# Plato_soldadura_328P.net
KiCad netlist of a schematic drawn in EAGLE
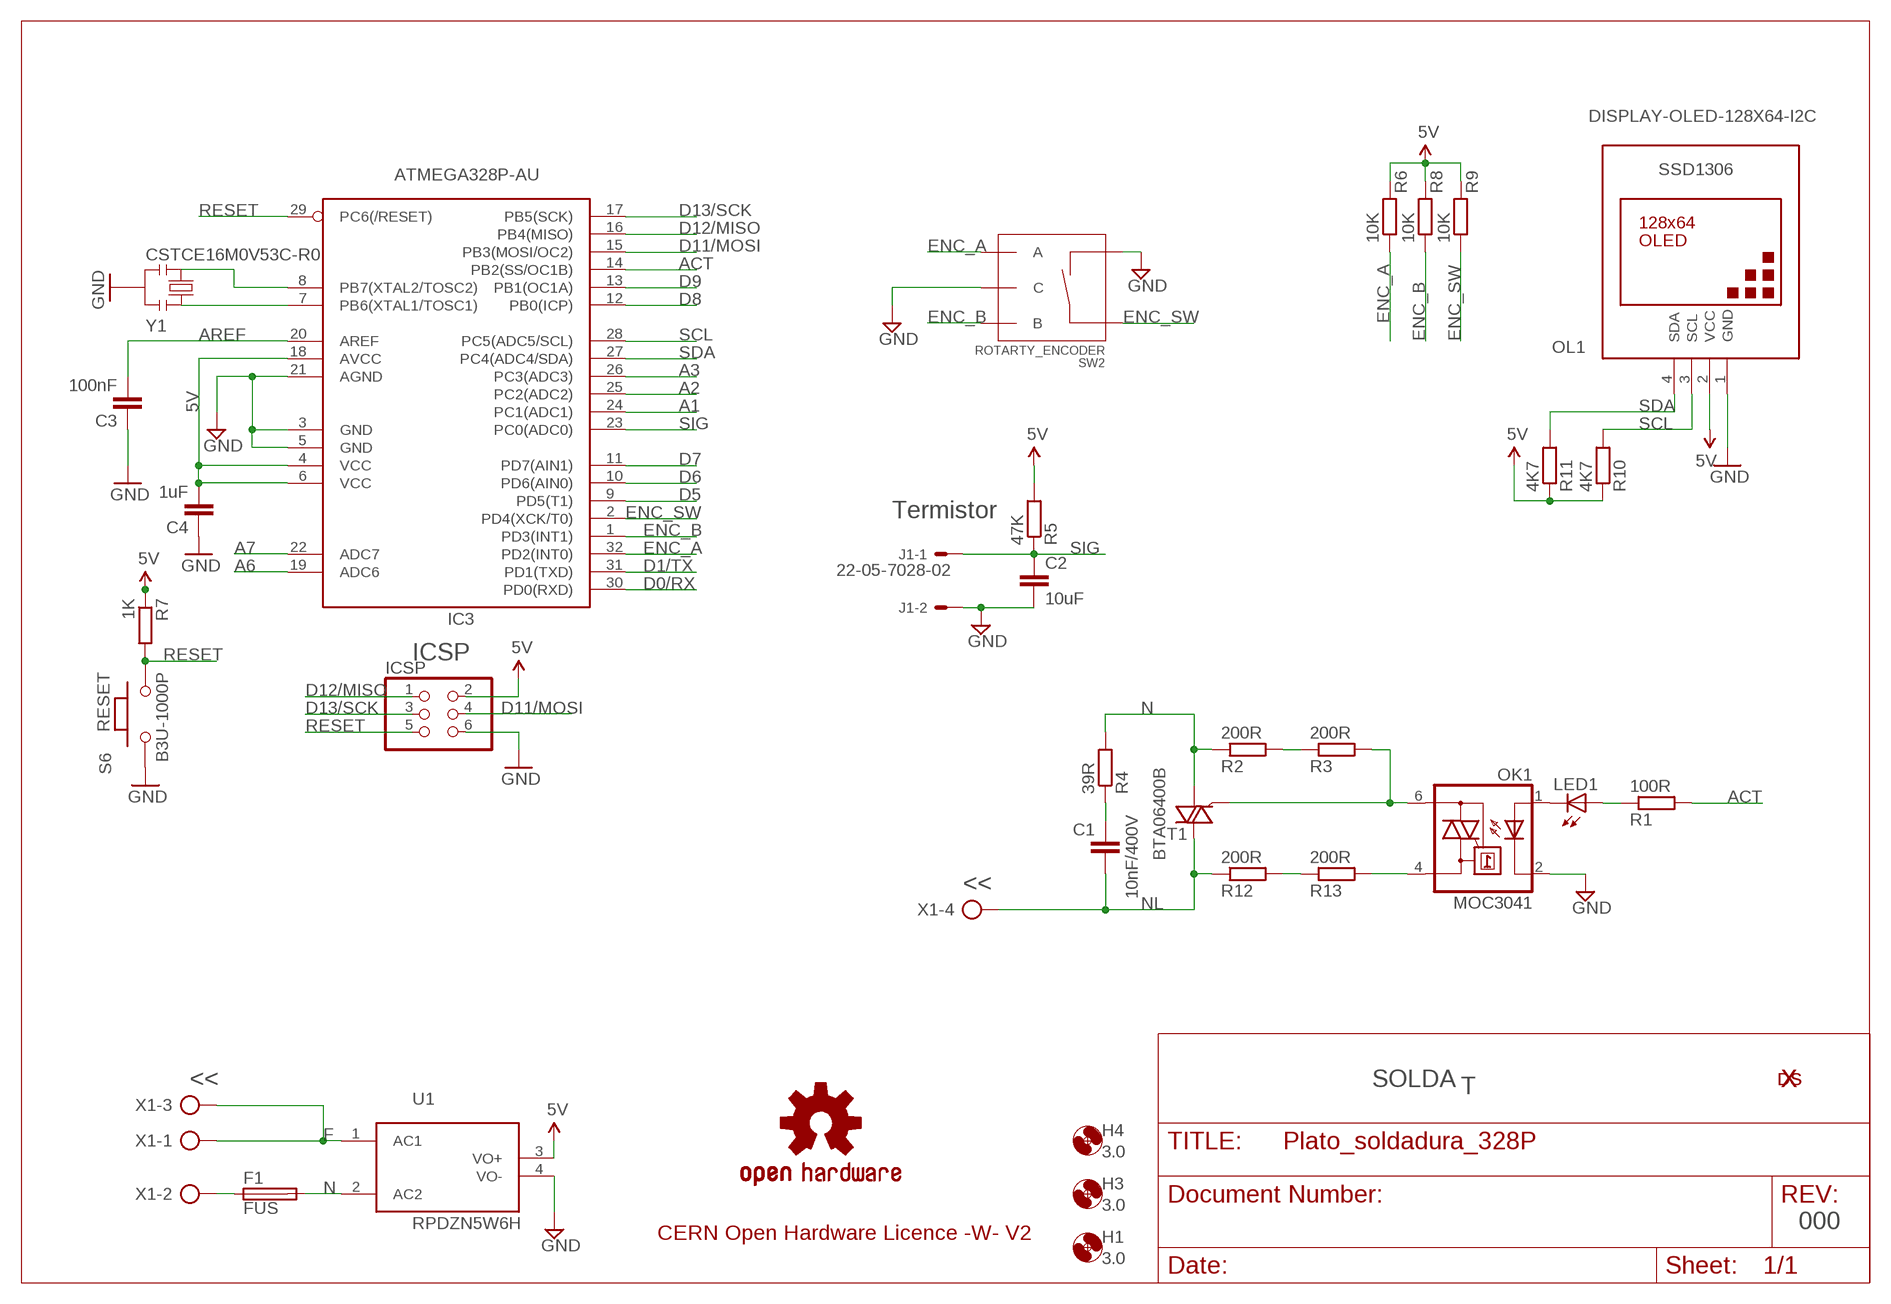
[diagram p0: schematic, sheet 1]

(export (version "E")
  (design (tool "Eeschema 10.0.6"))
  (components
    (comp (ref "C1")
      (value "10nF/400V")
      (footprint "eagle-import:C075-042X103")
      (libsource (lib "eagle-import") (part "C-EU075-042X103"))
    )
    (comp (ref "C2")
      (value "10uF")
      (footprint "eagle-import:C1206")
      (libsource (lib "eagle-import") (part "C-EUC1206"))
    )
    (comp (ref "C3")
      (value "100nF")
      (footprint "eagle-import:C0603")
      (libsource (lib "eagle-import") (part "C-EUC0603"))
    )
    (comp (ref "C4")
      (value "1uF")
      (footprint "eagle-import:C0603")
      (libsource (lib "eagle-import") (part "C-EUC0603"))
    )
    (comp (ref "F1")
      (value "FUS")
      (footprint "eagle-import:TE5")
      (libsource (lib "eagle-import") (part "FUSETE5"))
    )
    (comp (ref "H1")
      (value "3.0")
      (footprint "eagle-import:3,0")
      (libsource (lib "eagle-import") (part "MOUNT-HOLE3.0"))
    )
    (comp (ref "H3")
      (value "3.0")
      (footprint "eagle-import:3,0")
      (libsource (lib "eagle-import") (part "MOUNT-HOLE3.0"))
    )
    (comp (ref "H4")
      (value "3.0")
      (footprint "eagle-import:3,0")
      (libsource (lib "eagle-import") (part "MOUNT-HOLE3.0"))
    )
    (comp (ref "IC3")
      (value "ATMEGA328P-AU")
      (footprint "eagle-import:TQFP32-08")
      (libsource (lib "eagle-import") (part "0265_ATMEGA328P-AU"))
    )
    (comp (ref "ICSP")
      (value "0114_PH254-203DF118A00V")
      (footprint "eagle-import:2X03")
      (fields (field (name "PART_NUMBER") "PH254-203DF118A00V"))
      (libsource (lib "eagle-import") (part "0114_PH254-203DF118A00V"))
    )
    (comp (ref "J1")
      (value "22-05-7028-02")
      (footprint "eagle-import:7395-02")
      (libsource (lib "eagle-import") (part "22-?-0205-7028"))
    )
    (comp (ref "LED1")
      (value "LEDCHIP-LED0603")
      (footprint "eagle-import:CHIP-LED0603")
      (libsource (lib "eagle-import") (part "LEDCHIP-LED0603"))
    )
    (comp (ref "LOGO2")
      (value "OSHW-LOGOL")
      (footprint "eagle-import:ESCORNA_LBRESCORNA_CPU_2_10_SPARKFUN-AESTHETICS_OSHW-LOGO-L")
      (libsource (lib "eagle-import") (part "OSHW-LOGOL"))
    )
    (comp (ref "OK1")
      (value "MOC3041")
      (footprint "eagle-import:DIL06")
      (fields (field (name "MF") "VISHAY/TELEFUNKEN") (field (name "MPN") "IL410"))
      (libsource (lib "eagle-import") (part "IL410"))
    )
    (comp (ref "OL1")
      (value "DISPLAY-OLED-128X64-I2C")
      (footprint "eagle-import:DISPLAY-OLED-128X64-I2C")
      (libsource (lib "eagle-import") (part "DISPLAY-OLED-128X64-I2C"))
    )
    (comp (ref "R1")
      (value "100R")
      (footprint "eagle-import:R0603")
      (libsource (lib "eagle-import") (part "R-EU_R0603"))
    )
    (comp (ref "R2")
      (value "200R")
      (footprint "eagle-import:R1206")
      (libsource (lib "eagle-import") (part "R-EU_R1206"))
    )
    (comp (ref "R3")
      (value "200R")
      (footprint "eagle-import:R1206")
      (libsource (lib "eagle-import") (part "R-EU_R1206"))
    )
    (comp (ref "R4")
      (value "39R")
      (footprint "eagle-import:0204_7")
      (libsource (lib "eagle-import") (part "R-EU_0204/7"))
    )
    (comp (ref "R5")
      (value "47K")
      (footprint "eagle-import:R0603")
      (libsource (lib "eagle-import") (part "R-EU_R0603"))
    )
    (comp (ref "R6")
      (value "10K")
      (footprint "eagle-import:R0603")
      (libsource (lib "eagle-import") (part "R-EU_R0603"))
    )
    (comp (ref "R7")
      (value "1K")
      (footprint "eagle-import:R0603")
      (libsource (lib "eagle-import") (part "R-EU_R0603"))
    )
    (comp (ref "R8")
      (value "10K")
      (footprint "eagle-import:R0603")
      (libsource (lib "eagle-import") (part "R-EU_R0603"))
    )
    (comp (ref "R9")
      (value "10K")
      (footprint "eagle-import:R0603")
      (libsource (lib "eagle-import") (part "R-EU_R0603"))
    )
    (comp (ref "R10")
      (value "4K7")
      (footprint "eagle-import:R0603")
      (libsource (lib "eagle-import") (part "R-EU_R0603"))
    )
    (comp (ref "R11")
      (value "4K7")
      (footprint "eagle-import:R0603")
      (libsource (lib "eagle-import") (part "R-EU_R0603"))
    )
    (comp (ref "R12")
      (value "200R")
      (footprint "eagle-import:R1206")
      (libsource (lib "eagle-import") (part "R-EU_R1206"))
    )
    (comp (ref "R13")
      (value "200R")
      (footprint "eagle-import:R1206")
      (libsource (lib "eagle-import") (part "R-EU_R1206"))
    )
    (comp (ref "S6")
      (value "B3U-1000P")
      (footprint "eagle-import:SMD_157SW")
      (fields (field (name "PART_NUMBER") "IT-1185AP1C-160G-G_T&R"))
      (libsource (lib "eagle-import") (part "0173_IT-1185AP1C-160G-G_T&R"))
    )
    (comp (ref "SW2")
      (value "ROTARTY_ENCODER")
      (footprint "eagle-import:ROTARY_ENC_PLAIN")
      (libsource (lib "eagle-import") (part "ROTARTY_ENCODER"))
    )
    (comp (ref "T1")
      (value "BTA06400B")
      (footprint "eagle-import:TO220AB")
      (libsource (lib "eagle-import") (part "BT136"))
    )
    (comp (ref "U$7")
      (value "XDESIG_XDESIG5MM")
      (footprint "eagle-import:XDESIG_XDESIG_CU")
      (libsource (lib "eagle-import") (part "XDESIG_XDESIG5MM"))
    )
    (comp (ref "U$8")
      (value "XDESIG_XDESIG21")
      (footprint "eagle-import:XDESIG_XDESIG")
      (libsource (lib "eagle-import") (part "XDESIG_XDESIG21"))
    )
    (comp (ref "U1")
      (value "RPDZN5W6H")
      (footprint "eagle-import:RPDZN5W6H")
      (libsource (lib "eagle-import") (part "RPDZN5W6H"))
    )
    (comp (ref "X1")
      (value "AK500/4-H")
      (footprint "eagle-import:AK500_4-H")
      (libsource (lib "eagle-import") (part "AK500/4-H"))
    )
    (comp (ref "Y1")
      (value "CSTCE16M0V53C-R0")
      (footprint "eagle-import:RESONATOR")
      (fields (field (name "PART_NUMBER") "CSTCE16M0V53-R0"))
      (libsource (lib "eagle-import") (part "0011_CSTCE16M0V53-R0"))
    )
  )
  (nets
    (net (code "1") (name "/A1") (class "Default")
      (node (ref "IC3") (pin "24") (pinfunction "PC1(ADC1)_24") (pintype "bidirectional"))
    )
    (net (code "2") (name "/A2") (class "Default")
      (node (ref "IC3") (pin "25") (pinfunction "PC2(ADC2)_25") (pintype "bidirectional"))
    )
    (net (code "3") (name "/A3") (class "Default")
      (node (ref "IC3") (pin "26") (pinfunction "PC3(ADC3)_26") (pintype "bidirectional"))
    )
    (net (code "4") (name "/A6") (class "Default")
      (node (ref "IC3") (pin "19") (pinfunction "ADC6_19") (pintype "bidirectional"))
    )
    (net (code "5") (name "/A7") (class "Default")
      (node (ref "IC3") (pin "22") (pinfunction "ADC7_22") (pintype "bidirectional"))
    )
    (net (code "6") (name "/ACT") (class "Default")
      (node (ref "IC3") (pin "14") (pinfunction "PB2(SS/OC1B)_14") (pintype "bidirectional"))
      (node (ref "R1") (pin "2") (pinfunction "2_2") (pintype "passive"))
    )
    (net (code "7") (name "/AREF") (class "Default")
      (node (ref "C3") (pin "2") (pinfunction "2_2") (pintype "passive"))
      (node (ref "IC3") (pin "20") (pinfunction "AREF_20") (pintype "bidirectional"))
    )
    (net (code "8") (name "/D0{slash}RX") (class "Default")
      (node (ref "IC3") (pin "30") (pinfunction "PD0(RXD)_30") (pintype "bidirectional"))
    )
    (net (code "9") (name "/D1{slash}TX") (class "Default")
      (node (ref "IC3") (pin "31") (pinfunction "PD1(TXD)_31") (pintype "bidirectional"))
    )
    (net (code "10") (name "/D5") (class "Default")
      (node (ref "IC3") (pin "9") (pinfunction "PD5(T1)_9") (pintype "bidirectional"))
    )
    (net (code "11") (name "/D6") (class "Default")
      (node (ref "IC3") (pin "10") (pinfunction "PD6(AIN0)_10") (pintype "bidirectional"))
    )
    (net (code "12") (name "/D7") (class "Default")
      (node (ref "IC3") (pin "11") (pinfunction "PD7(AIN1)_11") (pintype "bidirectional"))
    )
    (net (code "13") (name "/D8") (class "Default")
      (node (ref "IC3") (pin "12") (pinfunction "PB0(ICP)_12") (pintype "bidirectional"))
    )
    (net (code "14") (name "/D9") (class "Default")
      (node (ref "IC3") (pin "13") (pinfunction "PB1(OC1A)_13") (pintype "bidirectional"))
    )
    (net (code "15") (name "/D11{slash}MOSI") (class "Default")
      (node (ref "IC3") (pin "15") (pinfunction "PB3(MOSI/OC2)_15") (pintype "bidirectional"))
      (node (ref "ICSP") (pin "4") (pinfunction "4_4") (pintype "passive"))
    )
    (net (code "16") (name "/D12{slash}MISO") (class "Default")
      (node (ref "IC3") (pin "16") (pinfunction "PB4(MISO)_16") (pintype "bidirectional"))
      (node (ref "ICSP") (pin "1") (pinfunction "1_1") (pintype "passive"))
    )
    (net (code "17") (name "/D13{slash}SCK") (class "Default")
      (node (ref "IC3") (pin "17") (pinfunction "PB5(SCK)_17") (pintype "bidirectional"))
      (node (ref "ICSP") (pin "3") (pinfunction "3_3") (pintype "passive"))
    )
    (net (code "18") (name "/ENC_A") (class "Default")
      (node (ref "IC3") (pin "32") (pinfunction "PD2(INT0)_32") (pintype "bidirectional"))
      (node (ref "R6") (pin "1") (pinfunction "1_1") (pintype "passive"))
      (node (ref "SW2") (pin "A") (pinfunction "A_A") (pintype "bidirectional"))
    )
    (net (code "19") (name "/ENC_B") (class "Default")
      (node (ref "IC3") (pin "1") (pinfunction "PD3(INT1)_1") (pintype "bidirectional"))
      (node (ref "R8") (pin "1") (pinfunction "1_1") (pintype "passive"))
      (node (ref "SW2") (pin "B") (pinfunction "B_B") (pintype "bidirectional"))
    )
    (net (code "20") (name "/ENC_SW") (class "Default")
      (node (ref "IC3") (pin "2") (pinfunction "PD4(XCK/T0)_2") (pintype "bidirectional"))
      (node (ref "R9") (pin "1") (pinfunction "1_1") (pintype "passive"))
      (node (ref "SW2") (pin "SW+") (pinfunction "SW+_SW+") (pintype "bidirectional"))
    )
    (net (code "21") (name "/F") (class "Default")
      (node (ref "U1") (pin "1") (pinfunction "AC1_1") (pintype "bidirectional"))
      (node (ref "X1") (pin "1") (pinfunction "KL_1") (pintype "passive"))
      (node (ref "X1") (pin "3") (pinfunction "KL_3") (pintype "passive"))
    )
    (net (code "22") (name "/N") (class "Default")
      (node (ref "F1") (pin "2") (pinfunction "2_2") (pintype "passive"))
      (node (ref "R2") (pin "1") (pinfunction "1_1") (pintype "passive"))
      (node (ref "R4") (pin "2") (pinfunction "2_2") (pintype "passive"))
      (node (ref "T1") (pin "1") (pinfunction "A1_1") (pintype "passive"))
      (node (ref "U1") (pin "2") (pinfunction "AC2_2") (pintype "bidirectional"))
    )
    (net (code "23") (name "/NL") (class "Default")
      (node (ref "C1") (pin "2") (pinfunction "2_2") (pintype "passive"))
      (node (ref "R12") (pin "1") (pinfunction "1_1") (pintype "passive"))
      (node (ref "T1") (pin "2") (pinfunction "A2_2") (pintype "passive"))
      (node (ref "X1") (pin "4") (pinfunction "KL_4") (pintype "passive"))
    )
    (net (code "24") (name "/RESET") (class "Default")
      (node (ref "IC3") (pin "29") (pinfunction "PC6(/RESET)_29") (pintype "bidirectional"))
      (node (ref "ICSP") (pin "5") (pinfunction "5_5") (pintype "passive"))
      (node (ref "R7") (pin "2") (pinfunction "2_2") (pintype "passive"))
      (node (ref "S6") (pin "2") (pinfunction "2_2") (pintype "passive"))
    )
    (net (code "25") (name "/SCL") (class "Default")
      (node (ref "IC3") (pin "28") (pinfunction "PC5(ADC5/SCL)_28") (pintype "bidirectional"))
      (node (ref "OL1") (pin "3") (pinfunction "SCL_3") (pintype "bidirectional"))
      (node (ref "R10") (pin "2") (pinfunction "2_2") (pintype "passive"))
    )
    (net (code "26") (name "/SDA") (class "Default")
      (node (ref "IC3") (pin "27") (pinfunction "PC4(ADC4/SDA)_27") (pintype "bidirectional"))
      (node (ref "OL1") (pin "4") (pinfunction "SDA_4") (pintype "bidirectional"))
      (node (ref "R11") (pin "2") (pinfunction "2_2") (pintype "passive"))
    )
    (net (code "27") (name "/SIG") (class "Default")
      (node (ref "C2") (pin "1") (pinfunction "1_1") (pintype "passive"))
      (node (ref "IC3") (pin "23") (pinfunction "PC0(ADC0)_23") (pintype "bidirectional"))
      (node (ref "J1") (pin "1") (pinfunction "S_1") (pintype "passive"))
      (node (ref "R5") (pin "1") (pinfunction "1_1") (pintype "passive"))
    )
    (net (code "28") (name "5V") (class "Default")
      (node (ref "C4") (pin "2") (pinfunction "2_2") (pintype "passive"))
      (node (ref "IC3") (pin "18") (pinfunction "AVCC_18") (pintype "bidirectional"))
      (node (ref "IC3") (pin "4") (pinfunction "VCC_4") (pintype "bidirectional"))
      (node (ref "IC3") (pin "6") (pinfunction "VCC_6") (pintype "bidirectional"))
      (node (ref "ICSP") (pin "2") (pinfunction "2_2") (pintype "passive"))
      (node (ref "OL1") (pin "2") (pinfunction "VCC_2") (pintype "power_in"))
      (node (ref "R10") (pin "1") (pinfunction "1_1") (pintype "passive"))
      (node (ref "R11") (pin "1") (pinfunction "1_1") (pintype "passive"))
      (node (ref "R5") (pin "2") (pinfunction "2_2") (pintype "passive"))
      (node (ref "R6") (pin "2") (pinfunction "2_2") (pintype "passive"))
      (node (ref "R7") (pin "1") (pinfunction "1_1") (pintype "passive"))
      (node (ref "R8") (pin "2") (pinfunction "2_2") (pintype "passive"))
      (node (ref "R9") (pin "2") (pinfunction "2_2") (pintype "passive"))
      (node (ref "U1") (pin "3") (pinfunction "VO+_3") (pintype "bidirectional"))
    )
    (net (code "29") (name "GND") (class "Default")
      (node (ref "C2") (pin "2") (pinfunction "2_2") (pintype "passive"))
      (node (ref "C3") (pin "1") (pinfunction "1_1") (pintype "passive"))
      (node (ref "C4") (pin "1") (pinfunction "1_1") (pintype "passive"))
      (node (ref "IC3") (pin "21") (pinfunction "AGND_21") (pintype "bidirectional"))
      (node (ref "IC3") (pin "3") (pinfunction "GND_3") (pintype "bidirectional"))
      (node (ref "IC3") (pin "5") (pinfunction "GND_5") (pintype "bidirectional"))
      (node (ref "ICSP") (pin "6") (pinfunction "6_6") (pintype "passive"))
      (node (ref "J1") (pin "2") (pinfunction "S_2") (pintype "passive"))
      (node (ref "OK1") (pin "2") (pinfunction "C_2") (pintype "passive"))
      (node (ref "OL1") (pin "1") (pinfunction "GND_1") (pintype "power_in"))
      (node (ref "S6") (pin "1") (pinfunction "1_1") (pintype "passive"))
      (node (ref "SW2") (pin "C") (pinfunction "C_C") (pintype "bidirectional"))
      (node (ref "SW2") (pin "SW-") (pinfunction "SW-_SW-") (pintype "bidirectional"))
      (node (ref "U1") (pin "4") (pinfunction "VO-_4") (pintype "bidirectional"))
      (node (ref "Y1") (pin "2") (pinfunction "2_2") (pintype "passive"))
    )
    (net (code "30") (name "Net-(C1-Pad1)") (class "Default")
      (node (ref "C1") (pin "1") (pinfunction "1_1") (pintype "passive"))
      (node (ref "R4") (pin "1") (pinfunction "1_1") (pintype "passive"))
    )
    (net (code "31") (name "Net-(IC3-PB6(XTAL1{slash}TOSC1))") (class "Default")
      (node (ref "IC3") (pin "7") (pinfunction "PB6(XTAL1/TOSC1)_7") (pintype "bidirectional"))
      (node (ref "Y1") (pin "1") (pinfunction "1_1") (pintype "passive"))
    )
    (net (code "32") (name "Net-(IC3-PB7(XTAL2{slash}TOSC2))") (class "Default")
      (node (ref "IC3") (pin "8") (pinfunction "PB7(XTAL2/TOSC2)_8") (pintype "bidirectional"))
      (node (ref "Y1") (pin "3") (pinfunction "3_3") (pintype "passive"))
    )
    (net (code "33") (name "Net-(LED1-PadA)") (class "Default")
      (node (ref "LED1") (pin "A") (pinfunction "A_A") (pintype "passive"))
      (node (ref "R1") (pin "1") (pinfunction "1_1") (pintype "passive"))
    )
    (net (code "34") (name "Net-(OK1-A)") (class "Default")
      (node (ref "LED1") (pin "C") (pinfunction "C_C") (pintype "passive"))
      (node (ref "OK1") (pin "1") (pinfunction "A_1") (pintype "passive"))
    )
    (net (code "35") (name "Net-(OK1-A1)") (class "Default")
      (node (ref "OK1") (pin "4") (pinfunction "A1_4") (pintype "passive"))
      (node (ref "R13") (pin "2") (pinfunction "2_2") (pintype "passive"))
    )
    (net (code "36") (name "Net-(OK1-A2)") (class "Default")
      (node (ref "OK1") (pin "6") (pinfunction "A2_6") (pintype "passive"))
      (node (ref "R3") (pin "2") (pinfunction "2_2") (pintype "passive"))
      (node (ref "T1") (pin "3") (pinfunction "G_3") (pintype "passive"))
    )
    (net (code "37") (name "Net-(R2-Pad2)") (class "Default")
      (node (ref "R2") (pin "2") (pinfunction "2_2") (pintype "passive"))
      (node (ref "R3") (pin "1") (pinfunction "1_1") (pintype "passive"))
    )
    (net (code "38") (name "Net-(R12-Pad2)") (class "Default")
      (node (ref "R12") (pin "2") (pinfunction "2_2") (pintype "passive"))
      (node (ref "R13") (pin "1") (pinfunction "1_1") (pintype "passive"))
    )
    (net (code "39") (name "Net-(X1B-KL)") (class "Default")
      (node (ref "F1") (pin "1") (pinfunction "1_1") (pintype "passive"))
      (node (ref "X1") (pin "2") (pinfunction "KL_2") (pintype "passive"))
    )
  )
)
